# External_Hardware.net
KiCad netlist of a schematic drawn in Altium Designer
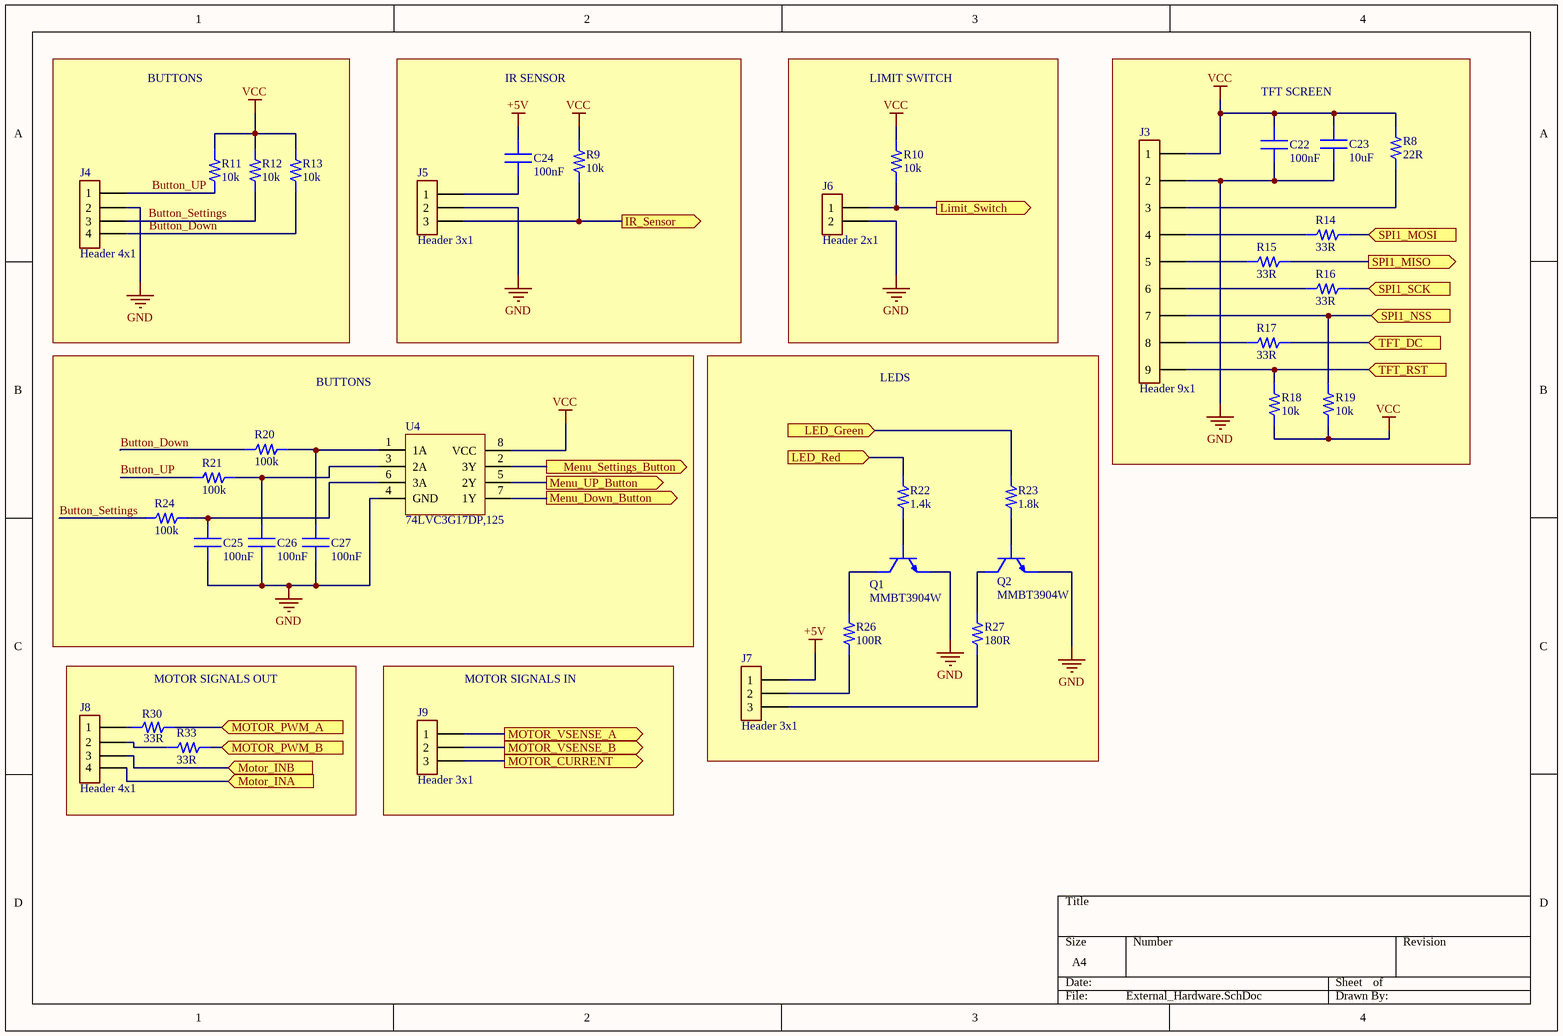
[diagram p0: External_Hardware.SchDoc]

(export (version "E")
  (design (tool "Eeschema 10.0.6"))
  (components
    (comp (ref "C22")
      (value "100nF")
      (footprint "CAPC 0603 1608X90N")
      (description "MLCC (1608) 0603 100nF 25VDC ±10% X7R")
      (fields (field (name "TOLERANCE") "±10%") (field (name "MANUFACTURER") "YAGEO"))
      (libsource (lib "Chicken_Coop_Door_Main_Board_V3") (part "CAP 0603 100nF CC0603KPX7R8BB104"))
    )
    (comp (ref "C23")
      (value "10uF")
      (footprint "CAPC1608X90N 0603")
      (description "MLCC (1608) 0603 10uF 10VDC ±10% X5R")
      (fields (field (name "TOLERANCE") "±10 %") (field (name "MANUFACTURER") "SAMSUNG"))
      (libsource (lib "Chicken_Coop_Door_Main_Board_V3") (part "CAP 0603 10uF CL10A106KP8NNNC"))
    )
    (comp (ref "C24")
      (value "100nF")
      (footprint "CAPC 0603 1608X90N")
      (description "MLCC (1608) 0603 100nF 25VDC ±10% X7R")
      (fields (field (name "TOLERANCE") "±10%") (field (name "MANUFACTURER") "YAGEO"))
      (libsource (lib "Chicken_Coop_Door_Main_Board_V3") (part "CAP 0603 100nF CC0603KPX7R8BB104"))
    )
    (comp (ref "C25")
      (value "100nF")
      (footprint "CAPC 0603 1608X90N")
      (description "MLCC (1608) 0603 100nF 25VDC ±10% X7R")
      (fields (field (name "TOLERANCE") "±10%") (field (name "MANUFACTURER") "YAGEO"))
      (libsource (lib "Chicken_Coop_Door_Main_Board_V3") (part "CAP 0603 100nF CC0603KPX7R8BB104"))
    )
    (comp (ref "C26")
      (value "100nF")
      (footprint "CAPC 0603 1608X90N")
      (description "MLCC (1608) 0603 100nF 25VDC ±10% X7R")
      (fields (field (name "TOLERANCE") "±10%") (field (name "MANUFACTURER") "YAGEO"))
      (libsource (lib "Chicken_Coop_Door_Main_Board_V3") (part "CAP 0603 100nF CC0603KPX7R8BB104"))
    )
    (comp (ref "C27")
      (value "100nF")
      (footprint "CAPC 0603 1608X90N")
      (description "MLCC (1608) 0603 100nF 25VDC ±10% X7R")
      (fields (field (name "TOLERANCE") "±10%") (field (name "MANUFACTURER") "YAGEO"))
      (libsource (lib "Chicken_Coop_Door_Main_Board_V3") (part "CAP 0603 100nF CC0603KPX7R8BB104"))
    )
    (comp (ref "J3")
      (value "Header 9x1")
      (footprint "Header 9x1 JST_B9B-PH-K-S")
      (description "CON.T.B.2.00MM 9P 180C MALE WHITE CONNFLY")
      (fields (field (name "MANUFACTURER") "CONNFLY"))
      (libsource (lib "Chicken_Coop_Door_Main_Board_V3") (part "Header 9x1 DS1066-9MVW6S"))
    )
    (comp (ref "J4")
      (value "Header 4x1")
      (footprint "JST_B4B-PH-K-S 1x4 Header")
      (description "CON.T.B.2MM 4P 180C MALE WHITE CONNFLY")
      (fields (field (name "MANUFACTURER") "CONNFLY"))
      (libsource (lib "Chicken_Coop_Door_Main_Board_V3") (part "Header 4x1 DS1066-4MVW6X"))
    )
    (comp (ref "J5")
      (value "Header 3x1")
      (footprint "JST_B3B-PH-K-S 1x3 Header")
      (description "CON.T.B.2.00MM 3P 180C MALE CONNFLY")
      (fields (field (name "MANUFACTURER") "CONNFLY"))
      (libsource (lib "Chicken_Coop_Door_Main_Board_V3") (part "Header 3x1 DS1066-3MVW6X"))
    )
    (comp (ref "J6")
      (value "Header 2x1")
      (footprint "JST_B2B-PH-K-S 1x2 Header")
      (description "CON.T.B.2.00MM 2P 180C MALE CONNFLY")
      (fields (field (name "MANUFACTURER") "CONNFLY"))
      (libsource (lib "Chicken_Coop_Door_Main_Board_V3") (part "Header 2x1 DS1066-2MVW6X"))
    )
    (comp (ref "J7")
      (value "Header 3x1")
      (footprint "JST_B3B-PH-K-S 1x3 Header")
      (description "CON.T.B.2.00MM 3P 180C MALE CONNFLY")
      (fields (field (name "MANUFACTURER") "CONNFLY"))
      (libsource (lib "Chicken_Coop_Door_Main_Board_V3") (part "Header 3x1 DS1066-3MVW6X"))
    )
    (comp (ref "J8")
      (value "Header 4x1")
      (footprint "JST_B4B-PH-K-S 1x4 Header")
      (description "CON.T.B.2MM 4P 180C MALE WHITE CONNFLY")
      (fields (field (name "MANUFACTURER") "CONNFLY"))
      (libsource (lib "Chicken_Coop_Door_Main_Board_V3") (part "Header 4x1 DS1066-4MVW6X"))
    )
    (comp (ref "J9")
      (value "Header 3x1")
      (footprint "JST_B3B-PH-K-S 1x3 Header")
      (description "CON.T.B.2.00MM 3P 180C MALE CONNFLY")
      (fields (field (name "MANUFACTURER") "CONNFLY"))
      (libsource (lib "Chicken_Coop_Door_Main_Board_V3") (part "Header 3x1 DS1066-3MVW6X"))
    )
    (comp (ref "Q1")
      (value "MMBT3904W")
      (footprint "MMBT3904_PNJ")
      (description "Bipolar (BJT) Transistor NPN 40 V 200 mA 150 mW Surface Mount SOT-323")
      (fields (field (name "MANUFACTURER") "Panjit International Inc."))
      (libsource (lib "Chicken_Coop_Door_Main_Board_V3") (part "NPN Transistor MMBT3904W"))
    )
    (comp (ref "Q2")
      (value "MMBT3904W")
      (footprint "MMBT3904_PNJ")
      (description "Bipolar (BJT) Transistor NPN 40 V 200 mA 150 mW Surface Mount SOT-323")
      (fields (field (name "MANUFACTURER") "Panjit International Inc."))
      (libsource (lib "Chicken_Coop_Door_Main_Board_V3") (part "NPN Transistor MMBT3904W"))
    )
    (comp (ref "R8")
      (value "22R")
      (footprint "RES 0603 ROYALOHM")
      (description "RES.(1608) 0603 22 Ohms 5% 1/10W-S 200PPM")
      (fields (field (name "TOLERANCE") "±5%") (field (name "MANUFACTURER") "ROYALOHM"))
      (libsource (lib "Chicken_Coop_Door_Main_Board_V3") (part "RES 0603 22 Ohms 0603SAJ0220T5E"))
    )
    (comp (ref "R9")
      (value "10k")
      (footprint "RES 0603 ROYALOHM")
      (description "RES.(1608) 0603 10K Ohms 5% 1/10W-S 100PPM")
      (fields (field (name "TOLERANCE") "±5 %") (field (name "MANUFACTURER") "ROYALOHM"))
      (libsource (lib "Chicken_Coop_Door_Main_Board_V3") (part "RES 0603 10k 0603SAJ0103T5E"))
    )
    (comp (ref "R10")
      (value "10k")
      (footprint "RES 0603 ROYALOHM")
      (description "RES.(1608) 0603 10K Ohms 5% 1/10W-S 100PPM")
      (fields (field (name "TOLERANCE") "±5 %") (field (name "MANUFACTURER") "ROYALOHM"))
      (libsource (lib "Chicken_Coop_Door_Main_Board_V3") (part "RES 0603 10k 0603SAJ0103T5E"))
    )
    (comp (ref "R11")
      (value "10k")
      (footprint "RES 0603 ROYALOHM")
      (description "RES.(1608) 0603 10K Ohms 5% 1/10W-S 100PPM")
      (fields (field (name "TOLERANCE") "±5 %") (field (name "MANUFACTURER") "ROYALOHM"))
      (libsource (lib "Chicken_Coop_Door_Main_Board_V3") (part "RES 0603 10k 0603SAJ0103T5E"))
    )
    (comp (ref "R12")
      (value "10k")
      (footprint "RES 0603 ROYALOHM")
      (description "RES.(1608) 0603 10K Ohms 5% 1/10W-S 100PPM")
      (fields (field (name "TOLERANCE") "±5 %") (field (name "MANUFACTURER") "ROYALOHM"))
      (libsource (lib "Chicken_Coop_Door_Main_Board_V3") (part "RES 0603 10k 0603SAJ0103T5E"))
    )
    (comp (ref "R13")
      (value "10k")
      (footprint "RES 0603 ROYALOHM")
      (description "RES.(1608) 0603 10K Ohms 5% 1/10W-S 100PPM")
      (fields (field (name "TOLERANCE") "±5 %") (field (name "MANUFACTURER") "ROYALOHM"))
      (libsource (lib "Chicken_Coop_Door_Main_Board_V3") (part "RES 0603 10k 0603SAJ0103T5E"))
    )
    (comp (ref "R14")
      (value "33R")
      (footprint "RES 0603 ROYALOHM")
      (description "RES.(1608) 0603 33 Ohms 5% 1/10W-S 200PPM")
      (fields (field (name "TOLERANCE") "±5%") (field (name "MANUFACTURER") "ROYALOHM"))
      (libsource (lib "Chicken_Coop_Door_Main_Board_V3") (part "RES 0603 33 Ohms 0603SAJ0330T5E"))
    )
    (comp (ref "R15")
      (value "33R")
      (footprint "RES 0603 ROYALOHM")
      (description "RES.(1608) 0603 33 Ohms 5% 1/10W-S 200PPM")
      (fields (field (name "TOLERANCE") "±5%") (field (name "MANUFACTURER") "ROYALOHM"))
      (libsource (lib "Chicken_Coop_Door_Main_Board_V3") (part "RES 0603 33 Ohms 0603SAJ0330T5E"))
    )
    (comp (ref "R16")
      (value "33R")
      (footprint "RES 0603 ROYALOHM")
      (description "RES.(1608) 0603 33 Ohms 5% 1/10W-S 200PPM")
      (fields (field (name "TOLERANCE") "±5%") (field (name "MANUFACTURER") "ROYALOHM"))
      (libsource (lib "Chicken_Coop_Door_Main_Board_V3") (part "RES 0603 33 Ohms 0603SAJ0330T5E"))
    )
    (comp (ref "R17")
      (value "33R")
      (footprint "RES 0603 ROYALOHM")
      (description "RES.(1608) 0603 33 Ohms 5% 1/10W-S 200PPM")
      (fields (field (name "TOLERANCE") "±5%") (field (name "MANUFACTURER") "ROYALOHM"))
      (libsource (lib "Chicken_Coop_Door_Main_Board_V3") (part "RES 0603 33 Ohms 0603SAJ0330T5E"))
    )
    (comp (ref "R18")
      (value "10k")
      (footprint "RES 0603 ROYALOHM")
      (description "RES.(1608) 0603 10K Ohms 5% 1/10W-S 100PPM")
      (fields (field (name "TOLERANCE") "±5 %") (field (name "MANUFACTURER") "ROYALOHM"))
      (libsource (lib "Chicken_Coop_Door_Main_Board_V3") (part "RES 0603 10k 0603SAJ0103T5E"))
    )
    (comp (ref "R19")
      (value "10k")
      (footprint "RES 0603 ROYALOHM")
      (description "RES.(1608) 0603 10K Ohms 5% 1/10W-S 100PPM")
      (fields (field (name "TOLERANCE") "±5 %") (field (name "MANUFACTURER") "ROYALOHM"))
      (libsource (lib "Chicken_Coop_Door_Main_Board_V3") (part "RES 0603 10k 0603SAJ0103T5E"))
    )
    (comp (ref "R20")
      (value "100k")
      (footprint "RES 0603 ROYALOHM")
      (description "RES.(1608) 0603 100K Ohms 1% 1/10W-S 100PPM")
      (fields (field (name "TOLERANCE") "±5 %") (field (name "MANUFACTURER") "ROYALOHM"))
      (libsource (lib "Chicken_Coop_Door_Main_Board_V3") (part "RES 0603 100k 0603SAF1003T5E"))
    )
    (comp (ref "R21")
      (value "100k")
      (footprint "RES 0603 ROYALOHM")
      (description "RES.(1608) 0603 100K Ohms 1% 1/10W-S 100PPM")
      (fields (field (name "TOLERANCE") "±5 %") (field (name "MANUFACTURER") "ROYALOHM"))
      (libsource (lib "Chicken_Coop_Door_Main_Board_V3") (part "RES 0603 100k 0603SAF1003T5E"))
    )
    (comp (ref "R22")
      (value "1.4k")
      (footprint "RES 0603 ROYALOHM")
      (description "RES.(1608) 0603 1.4K Ohms 1% 1/10W-S 100PPM")
      (fields (field (name "TOLERANCE") "±1 %") (field (name "MANUFACTURER") "ROYALOHM"))
      (libsource (lib "Chicken_Coop_Door_Main_Board_V3") (part "RES 0603 1.4k 0603SAF1401T5E"))
    )
    (comp (ref "R23")
      (value "1.8k")
      (footprint "RES 0603 ROYALOHM")
      (description "RES.(1608) 0603 1.8K Ohms 1% 1/10W-S 100PPM")
      (fields (field (name "TOLERANCE") "±1 %") (field (name "MANUFACTURER") "ROYALOHM"))
      (libsource (lib "Chicken_Coop_Door_Main_Board_V3") (part "RES 0603 1.8k 0603SAF1801T5E"))
    )
    (comp (ref "R24")
      (value "100k")
      (footprint "RES 0603 ROYALOHM")
      (description "RES.(1608) 0603 100K Ohms 1% 1/10W-S 100PPM")
      (fields (field (name "TOLERANCE") "±5 %") (field (name "MANUFACTURER") "ROYALOHM"))
      (libsource (lib "Chicken_Coop_Door_Main_Board_V3") (part "RES 0603 100k 0603SAF1003T5E"))
    )
    (comp (ref "R26")
      (value "100R")
      (footprint "RES 0805 YAGEO C2012X60N")
      (description "RES.(2012) 0805 100 Ohms 1% 1/8W-S 200PPM")
      (fields (field (name "POWER") "1/8W") (field (name "TOLERANCE") "±1 %"))
      (libsource (lib "Chicken_Coop_Door_Main_Board_V3") (part "RES 0805 100R 0805S8F1000T5E"))
    )
    (comp (ref "R27")
      (value "180R")
      (footprint "RES 0805 YAGEO C2012X60N")
      (description "RES.(2012) 0805 180 Ohms 5% 1/8W-S 100PPM")
      (fields (field (name "POWER") "1/8W") (field (name "TOLERANCE") "±1 %"))
      (libsource (lib "Chicken_Coop_Door_Main_Board_V3") (part "RES 0805 180R 0805S8J0181T5E"))
    )
    (comp (ref "R30")
      (value "33R")
      (footprint "RES 0603 ROYALOHM")
      (description "RES.(1608) 0603 33 Ohms 5% 1/10W-S 200PPM")
      (fields (field (name "TOLERANCE") "±5%") (field (name "MANUFACTURER") "ROYALOHM"))
      (libsource (lib "Chicken_Coop_Door_Main_Board_V3") (part "RES 0603 33 Ohms 0603SAJ0330T5E"))
    )
    (comp (ref "R33")
      (value "33R")
      (footprint "RES 0603 ROYALOHM")
      (description "RES.(1608) 0603 33 Ohms 5% 1/10W-S 200PPM")
      (fields (field (name "TOLERANCE") "±5%") (field (name "MANUFACTURER") "ROYALOHM"))
      (libsource (lib "Chicken_Coop_Door_Main_Board_V3") (part "RES 0603 33 Ohms 0603SAJ0330T5E"))
    )
    (comp (ref "U4")
      (value "74LVC3G17DP,125")
      (footprint "Schmitt Triger 74LVC3G17DP,125 TSSOP8_SOT505-2_NEX")
      (description "Buffer, Non-Inverting 3 Element 1 Bit per Element Push-Pull Output 8-TSSOP")
      (fields (field (name "MANUFACTURER") "Nexperia USA Inc."))
      (libsource (lib "Chicken_Coop_Door_Main_Board_V3") (part "Schmitt Triger 74LVC3G17DP,125"))
    )
  )
  (nets
    (net (code "1") (name "+5V") (class "Default")
      (node (ref "C24") (pin "2") (pinfunction "2_2") (pintype "passive"))
      (node (ref "J7") (pin "1") (pinfunction "1_1") (pintype "passive"))
    )
    (net (code "2") (name "/Button_Down") (class "Default")
      (node (ref "J4") (pin "4") (pinfunction "4_4") (pintype "passive"))
      (node (ref "R13") (pin "1") (pinfunction "1_1") (pintype "passive"))
      (node (ref "R20") (pin "1") (pinfunction "1_1") (pintype "passive"))
    )
    (net (code "3") (name "/Button_Settings") (class "Default")
      (node (ref "J4") (pin "3") (pinfunction "3_3") (pintype "passive"))
      (node (ref "R12") (pin "1") (pinfunction "1_1") (pintype "passive"))
      (node (ref "R24") (pin "1") (pinfunction "1_1") (pintype "passive"))
    )
    (net (code "4") (name "/Button_UP") (class "Default")
      (node (ref "J4") (pin "1") (pinfunction "1_1") (pintype "passive"))
      (node (ref "R11") (pin "1") (pinfunction "1_1") (pintype "passive"))
      (node (ref "R21") (pin "1") (pinfunction "1_1") (pintype "passive"))
    )
    (net (code "5") (name "/IR_Sensor") (class "Default")
      (node (ref "J5") (pin "3") (pinfunction "3_3") (pintype "passive"))
      (node (ref "R9") (pin "1") (pinfunction "1_1") (pintype "passive"))
    )
    (net (code "6") (name "/LED_Green") (class "Default")
      (node (ref "R23") (pin "2") (pinfunction "2_2") (pintype "passive"))
    )
    (net (code "7") (name "/LED_Red") (class "Default")
      (node (ref "R22") (pin "2") (pinfunction "2_2") (pintype "passive"))
    )
    (net (code "8") (name "/Limit_Switch") (class "Default")
      (node (ref "J6") (pin "1") (pinfunction "1_1") (pintype "passive"))
      (node (ref "R10") (pin "1") (pinfunction "1_1") (pintype "passive"))
    )
    (net (code "9") (name "/MOTOR_CURRENT") (class "Default")
      (node (ref "J9") (pin "3") (pinfunction "3_3") (pintype "passive"))
    )
    (net (code "10") (name "/MOTOR_PWM_A") (class "Default")
      (node (ref "R30") (pin "2") (pinfunction "2_2") (pintype "passive"))
    )
    (net (code "11") (name "/MOTOR_PWM_B") (class "Default")
      (node (ref "R33") (pin "2") (pinfunction "2_2") (pintype "passive"))
    )
    (net (code "12") (name "/MOTOR_VSENSE_A") (class "Default")
      (node (ref "J9") (pin "1") (pinfunction "1_1") (pintype "passive"))
    )
    (net (code "13") (name "/MOTOR_VSENSE_B") (class "Default")
      (node (ref "J9") (pin "2") (pinfunction "2_2") (pintype "passive"))
    )
    (net (code "14") (name "/Menu_Down_Button") (class "Default")
      (node (ref "U4") (pin "7") (pinfunction "1Y_7") (pintype "passive"))
    )
    (net (code "15") (name "/Menu_Settings_Button") (class "Default")
      (node (ref "U4") (pin "2") (pinfunction "3Y_2") (pintype "passive"))
    )
    (net (code "16") (name "/Menu_UP_Button") (class "Default")
      (node (ref "U4") (pin "5") (pinfunction "2Y_5") (pintype "passive"))
    )
    (net (code "17") (name "/Motor_INA") (class "Default")
      (node (ref "J8") (pin "4") (pinfunction "4_4") (pintype "passive"))
    )
    (net (code "18") (name "/Motor_INB") (class "Default")
      (node (ref "J8") (pin "3") (pinfunction "3_3") (pintype "passive"))
    )
    (net (code "19") (name "/SPI1_MISO") (class "Default")
      (node (ref "R15") (pin "2") (pinfunction "2_2") (pintype "passive"))
    )
    (net (code "20") (name "/SPI1_MOSI") (class "Default")
      (node (ref "R14") (pin "2") (pinfunction "2_2") (pintype "passive"))
    )
    (net (code "21") (name "/SPI1_NSS") (class "Default")
      (node (ref "J3") (pin "7") (pinfunction "7_7") (pintype "passive"))
      (node (ref "R19") (pin "2") (pinfunction "2_2") (pintype "passive"))
    )
    (net (code "22") (name "/SPI1_SCK") (class "Default")
      (node (ref "R16") (pin "2") (pinfunction "2_2") (pintype "passive"))
    )
    (net (code "23") (name "/TFT_DC") (class "Default")
      (node (ref "R17") (pin "2") (pinfunction "2_2") (pintype "passive"))
    )
    (net (code "24") (name "/TFT_RST") (class "Default")
      (node (ref "J3") (pin "9") (pinfunction "9_9") (pintype "passive"))
      (node (ref "R18") (pin "2") (pinfunction "2_2") (pintype "passive"))
    )
    (net (code "25") (name "GND") (class "Default")
      (node (ref "C22") (pin "1") (pinfunction "1_1") (pintype "passive"))
      (node (ref "C23") (pin "1") (pinfunction "1_1") (pintype "passive"))
      (node (ref "C25") (pin "1") (pinfunction "1_1") (pintype "passive"))
      (node (ref "C26") (pin "2") (pinfunction "2_2") (pintype "passive"))
      (node (ref "C27") (pin "1") (pinfunction "1_1") (pintype "passive"))
      (node (ref "J3") (pin "2") (pinfunction "2_2") (pintype "passive"))
      (node (ref "J4") (pin "2") (pinfunction "2_2") (pintype "passive"))
      (node (ref "J5") (pin "2") (pinfunction "2_2") (pintype "passive"))
      (node (ref "J6") (pin "2") (pinfunction "2_2") (pintype "passive"))
      (node (ref "Q1") (pin "2") (pinfunction "Emitter_2") (pintype "passive"))
      (node (ref "Q2") (pin "2") (pinfunction "Emitter_2") (pintype "passive"))
      (node (ref "U4") (pin "4") (pinfunction "GND_4") (pintype "passive"))
    )
    (net (code "26") (name "Net-(C24-Pad1)") (class "Default")
      (node (ref "C24") (pin "1") (pinfunction "1_1") (pintype "passive"))
      (node (ref "J5") (pin "1") (pinfunction "1_1") (pintype "passive"))
    )
    (net (code "27") (name "Net-(J3-Pad3)") (class "Default")
      (node (ref "J3") (pin "3") (pinfunction "3_3") (pintype "passive"))
      (node (ref "R8") (pin "1") (pinfunction "1_1") (pintype "passive"))
    )
    (net (code "28") (name "Net-(J3-Pad4)") (class "Default")
      (node (ref "J3") (pin "4") (pinfunction "4_4") (pintype "passive"))
      (node (ref "R14") (pin "1") (pinfunction "1_1") (pintype "passive"))
    )
    (net (code "29") (name "Net-(J3-Pad5)") (class "Default")
      (node (ref "J3") (pin "5") (pinfunction "5_5") (pintype "passive"))
      (node (ref "R15") (pin "1") (pinfunction "1_1") (pintype "passive"))
    )
    (net (code "30") (name "Net-(J3-Pad6)") (class "Default")
      (node (ref "J3") (pin "6") (pinfunction "6_6") (pintype "passive"))
      (node (ref "R16") (pin "1") (pinfunction "1_1") (pintype "passive"))
    )
    (net (code "31") (name "Net-(J3-Pad8)") (class "Default")
      (node (ref "J3") (pin "8") (pinfunction "8_8") (pintype "passive"))
      (node (ref "R17") (pin "1") (pinfunction "1_1") (pintype "passive"))
    )
    (net (code "32") (name "Net-(J7-Pad2)") (class "Default")
      (node (ref "J7") (pin "2") (pinfunction "2_2") (pintype "passive"))
      (node (ref "R26") (pin "1") (pinfunction "1_1") (pintype "passive"))
    )
    (net (code "33") (name "Net-(J7-Pad3)") (class "Default")
      (node (ref "J7") (pin "3") (pinfunction "3_3") (pintype "passive"))
      (node (ref "R27") (pin "1") (pinfunction "1_1") (pintype "passive"))
    )
    (net (code "34") (name "Net-(J8-Pad1)") (class "Default")
      (node (ref "J8") (pin "1") (pinfunction "1_1") (pintype "passive"))
      (node (ref "R30") (pin "1") (pinfunction "1_1") (pintype "passive"))
    )
    (net (code "35") (name "Net-(J8-Pad2)") (class "Default")
      (node (ref "J8") (pin "2") (pinfunction "2_2") (pintype "passive"))
      (node (ref "R33") (pin "1") (pinfunction "1_1") (pintype "passive"))
    )
    (net (code "36") (name "Net-(Q1-Base)") (class "Default")
      (node (ref "Q1") (pin "1") (pinfunction "Base_1") (pintype "passive"))
      (node (ref "R22") (pin "1") (pinfunction "1_1") (pintype "passive"))
    )
    (net (code "37") (name "Net-(Q1-Collector)") (class "Default")
      (node (ref "Q1") (pin "3") (pinfunction "Collector_3") (pintype "passive"))
      (node (ref "R26") (pin "2") (pinfunction "2_2") (pintype "passive"))
    )
    (net (code "38") (name "Net-(Q2-Base)") (class "Default")
      (node (ref "Q2") (pin "1") (pinfunction "Base_1") (pintype "passive"))
      (node (ref "R23") (pin "1") (pinfunction "1_1") (pintype "passive"))
    )
    (net (code "39") (name "Net-(Q2-Collector)") (class "Default")
      (node (ref "Q2") (pin "3") (pinfunction "Collector_3") (pintype "passive"))
      (node (ref "R27") (pin "2") (pinfunction "2_2") (pintype "passive"))
    )
    (net (code "40") (name "Net-(U4-1A)") (class "Default")
      (node (ref "C27") (pin "2") (pinfunction "2_2") (pintype "passive"))
      (node (ref "R20") (pin "2") (pinfunction "2_2") (pintype "passive"))
      (node (ref "U4") (pin "1") (pinfunction "1A_1") (pintype "passive"))
    )
    (net (code "41") (name "Net-(U4-2A)") (class "Default")
      (node (ref "C26") (pin "1") (pinfunction "1_1") (pintype "passive"))
      (node (ref "R21") (pin "2") (pinfunction "2_2") (pintype "passive"))
      (node (ref "U4") (pin "3") (pinfunction "2A_3") (pintype "passive"))
    )
    (net (code "42") (name "Net-(U4-3A)") (class "Default")
      (node (ref "C25") (pin "2") (pinfunction "2_2") (pintype "passive"))
      (node (ref "R24") (pin "2") (pinfunction "2_2") (pintype "passive"))
      (node (ref "U4") (pin "6") (pinfunction "3A_6") (pintype "passive"))
    )
    (net (code "43") (name "VCC") (class "Default")
      (node (ref "C22") (pin "2") (pinfunction "2_2") (pintype "passive"))
      (node (ref "C23") (pin "2") (pinfunction "2_2") (pintype "passive"))
      (node (ref "J3") (pin "1") (pinfunction "1_1") (pintype "passive"))
      (node (ref "R10") (pin "2") (pinfunction "2_2") (pintype "passive"))
      (node (ref "R11") (pin "2") (pinfunction "2_2") (pintype "passive"))
      (node (ref "R12") (pin "2") (pinfunction "2_2") (pintype "passive"))
      (node (ref "R13") (pin "2") (pinfunction "2_2") (pintype "passive"))
      (node (ref "R18") (pin "1") (pinfunction "1_1") (pintype "passive"))
      (node (ref "R19") (pin "1") (pinfunction "1_1") (pintype "passive"))
      (node (ref "R8") (pin "2") (pinfunction "2_2") (pintype "passive"))
      (node (ref "R9") (pin "2") (pinfunction "2_2") (pintype "passive"))
      (node (ref "U4") (pin "8") (pinfunction "VCC_8") (pintype "passive"))
    )
  )
)
